# design.net
KiCad netlist of a schematic drawn in Altium Designer
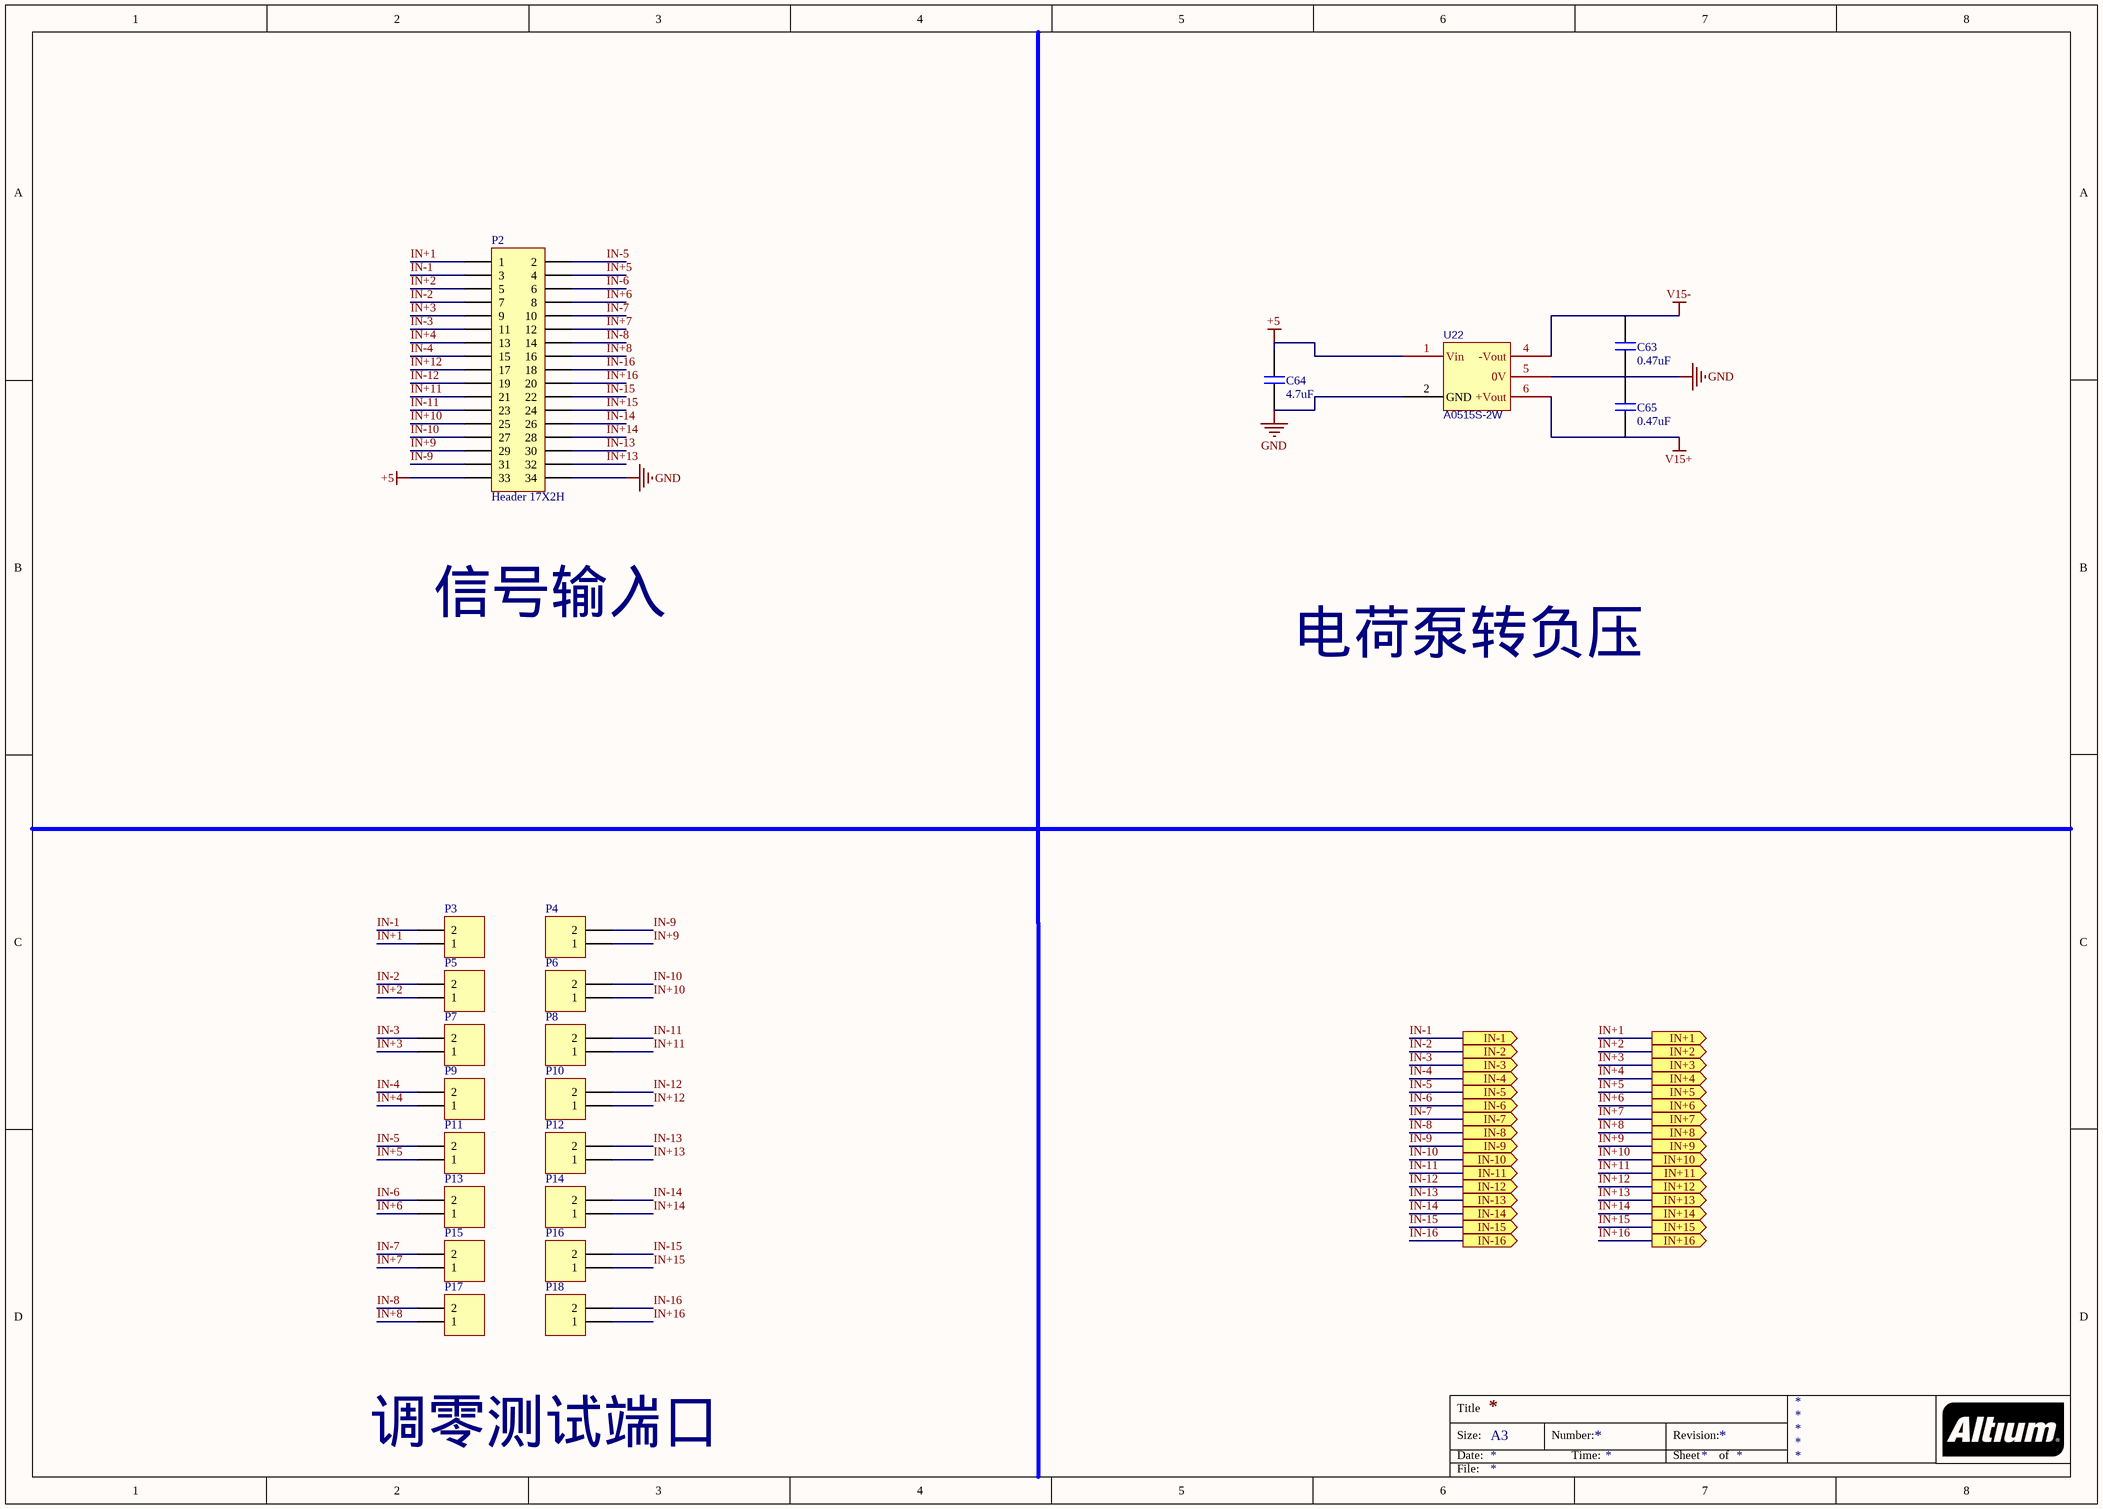
[diagram p0: 信号输入模块.SchDoc]

(export (version "E")
  (design (tool "Eeschema 10.0.6"))
  (components
    (comp (ref "C63")
      (value "0.47uF")
      (footprint "0805C")
      (description "普通电容")
      (libsource (lib "毕业设计") (part "CAP"))
    )
    (comp (ref "C64")
      (value "4.7uF")
      (footprint "0805C")
      (description "普通电容")
      (libsource (lib "毕业设计") (part "CAP"))
    )
    (comp (ref "C65")
      (value "0.47uF")
      (footprint "0805C")
      (description "普通电容")
      (libsource (lib "毕业设计") (part "CAP"))
    )
    (comp (ref "P2")
      (value "Header 17X2H")
      (footprint "HDR2X17")
      (description "Header, 17-Pin, Dual row, Right Angle")
      (fields (field (name "PUBLISHER") "Altium Limited"))
      (libsource (lib "Miscellaneous Connectors") (part "Header 17X2H"))
    )
    (comp (ref "P3")
      (value "Header 2H")
      (footprint "HDR-SMD_2P-P2.54-V-M-S4.8")
      (description "Header, 2-Pin, Right Angle")
      (fields (field (name "PUBLISHER") "Altium Limited"))
      (libsource (lib "") (part "Header 2H_1"))
    )
    (comp (ref "P4")
      (value "Header 2H")
      (footprint "HDR-SMD_2P-P2.54-V-M-S4.8")
      (description "Header, 2-Pin, Right Angle")
      (fields (field (name "PUBLISHER") "Altium Limited"))
      (libsource (lib "Miscellaneous Connectors") (part "Header 2H"))
    )
    (comp (ref "P5")
      (value "Header 2H")
      (footprint "HDR-SMD_2P-P2.54-V-M-S4.8")
      (description "Header, 2-Pin, Right Angle")
      (fields (field (name "PUBLISHER") "Altium Limited"))
      (libsource (lib "") (part "Header 2H_1"))
    )
    (comp (ref "P6")
      (value "Header 2H")
      (footprint "HDR-SMD_2P-P2.54-V-M-S4.8")
      (description "Header, 2-Pin, Right Angle")
      (fields (field (name "PUBLISHER") "Altium Limited"))
      (libsource (lib "Miscellaneous Connectors") (part "Header 2H"))
    )
    (comp (ref "P7")
      (value "Header 2H")
      (footprint "HDR-SMD_2P-P2.54-V-M-S4.8")
      (description "Header, 2-Pin, Right Angle")
      (fields (field (name "PUBLISHER") "Altium Limited"))
      (libsource (lib "") (part "Header 2H_1"))
    )
    (comp (ref "P8")
      (value "Header 2H")
      (footprint "HDR-SMD_2P-P2.54-V-M-S4.8")
      (description "Header, 2-Pin, Right Angle")
      (fields (field (name "PUBLISHER") "Altium Limited"))
      (libsource (lib "Miscellaneous Connectors") (part "Header 2H"))
    )
    (comp (ref "P9")
      (value "Header 2H")
      (footprint "HDR-SMD_2P-P2.54-V-M-S4.8")
      (description "Header, 2-Pin, Right Angle")
      (fields (field (name "PUBLISHER") "Altium Limited"))
      (libsource (lib "") (part "Header 2H_1"))
    )
    (comp (ref "P10")
      (value "Header 2H")
      (footprint "HDR-SMD_2P-P2.54-V-M-S4.8")
      (description "Header, 2-Pin, Right Angle")
      (fields (field (name "PUBLISHER") "Altium Limited"))
      (libsource (lib "Miscellaneous Connectors") (part "Header 2H"))
    )
    (comp (ref "P11")
      (value "Header 2H")
      (footprint "HDR-SMD_2P-P2.54-V-M-S4.8")
      (description "Header, 2-Pin, Right Angle")
      (fields (field (name "PUBLISHER") "Altium Limited"))
      (libsource (lib "") (part "Header 2H_1"))
    )
    (comp (ref "P12")
      (value "Header 2H")
      (footprint "HDR-SMD_2P-P2.54-V-M-S4.8")
      (description "Header, 2-Pin, Right Angle")
      (fields (field (name "PUBLISHER") "Altium Limited"))
      (libsource (lib "Miscellaneous Connectors") (part "Header 2H"))
    )
    (comp (ref "P13")
      (value "Header 2H")
      (footprint "HDR-SMD_2P-P2.54-V-M-S4.8")
      (description "Header, 2-Pin, Right Angle")
      (fields (field (name "PUBLISHER") "Altium Limited"))
      (libsource (lib "") (part "Header 2H_1"))
    )
    (comp (ref "P14")
      (value "Header 2H")
      (footprint "HDR-SMD_2P-P2.54-V-M-S4.8")
      (description "Header, 2-Pin, Right Angle")
      (fields (field (name "PUBLISHER") "Altium Limited"))
      (libsource (lib "Miscellaneous Connectors") (part "Header 2H"))
    )
    (comp (ref "P15")
      (value "Header 2H")
      (footprint "HDR-SMD_2P-P2.54-V-M-S4.8")
      (description "Header, 2-Pin, Right Angle")
      (fields (field (name "PUBLISHER") "Altium Limited"))
      (libsource (lib "") (part "Header 2H_1"))
    )
    (comp (ref "P16")
      (value "Header 2H")
      (footprint "HDR-SMD_2P-P2.54-V-M-S4.8")
      (description "Header, 2-Pin, Right Angle")
      (fields (field (name "PUBLISHER") "Altium Limited"))
      (libsource (lib "Miscellaneous Connectors") (part "Header 2H"))
    )
    (comp (ref "P17")
      (value "Header 2H")
      (footprint "HDR-SMD_2P-P2.54-V-M-S4.8")
      (description "Header, 2-Pin, Right Angle")
      (fields (field (name "PUBLISHER") "Altium Limited"))
      (libsource (lib "") (part "Header 2H_1"))
    )
    (comp (ref "P18")
      (value "Header 2H")
      (footprint "HDR-SMD_2P-P2.54-V-M-S4.8")
      (description "Header, 2-Pin, Right Angle")
      (fields (field (name "PUBLISHER") "Altium Limited"))
      (libsource (lib "Miscellaneous Connectors") (part "Header 2H"))
    )
    (comp (ref "U22")
      (value "A0515S-2W")
      (footprint "PWRM-TH_AXXXXS-2W")
      (description "5V升15V DC-DC")
      (fields (field (name "BOM_SUPPLIER PART") "C442557") (field (name "CONTRIBUTOR") "LCSC"))
      (libsource (lib "毕业设计") (part "A0515S-2W"))
    )
  )
  (nets
    (net (code "1") (name "+5") (class "Default")
      (node (ref "C64") (pin "2") (pinfunction "2_2") (pintype "passive"))
      (node (ref "P2") (pin "33") (pinfunction "33_33") (pintype "passive"))
      (node (ref "U22") (pin "1") (pinfunction "Vin_1") (pintype "passive"))
    )
    (net (code "2") (name "/IN+1") (class "Default")
      (node (ref "P2") (pin "1") (pinfunction "1_1") (pintype "passive"))
      (node (ref "P3") (pin "1") (pinfunction "1_1") (pintype "passive"))
    )
    (net (code "3") (name "/IN+2") (class "Default")
      (node (ref "P2") (pin "5") (pinfunction "5_5") (pintype "passive"))
      (node (ref "P5") (pin "1") (pinfunction "1_1") (pintype "passive"))
    )
    (net (code "4") (name "/IN+3") (class "Default")
      (node (ref "P2") (pin "9") (pinfunction "9_9") (pintype "passive"))
      (node (ref "P7") (pin "1") (pinfunction "1_1") (pintype "passive"))
    )
    (net (code "5") (name "/IN+4") (class "Default")
      (node (ref "P2") (pin "13") (pinfunction "13_13") (pintype "passive"))
      (node (ref "P9") (pin "1") (pinfunction "1_1") (pintype "passive"))
    )
    (net (code "6") (name "/IN+5") (class "Default")
      (node (ref "P11") (pin "1") (pinfunction "1_1") (pintype "passive"))
      (node (ref "P2") (pin "4") (pinfunction "4_4") (pintype "passive"))
    )
    (net (code "7") (name "/IN+6") (class "Default")
      (node (ref "P13") (pin "1") (pinfunction "1_1") (pintype "passive"))
      (node (ref "P2") (pin "8") (pinfunction "8_8") (pintype "passive"))
    )
    (net (code "8") (name "/IN+7") (class "Default")
      (node (ref "P15") (pin "1") (pinfunction "1_1") (pintype "passive"))
      (node (ref "P2") (pin "12") (pinfunction "12_12") (pintype "passive"))
    )
    (net (code "9") (name "/IN+8") (class "Default")
      (node (ref "P17") (pin "1") (pinfunction "1_1") (pintype "passive"))
      (node (ref "P2") (pin "16") (pinfunction "16_16") (pintype "passive"))
    )
    (net (code "10") (name "/IN+9") (class "Default")
      (node (ref "P2") (pin "29") (pinfunction "29_29") (pintype "passive"))
      (node (ref "P4") (pin "1") (pinfunction "1_1") (pintype "passive"))
    )
    (net (code "11") (name "/IN+10") (class "Default")
      (node (ref "P2") (pin "25") (pinfunction "25_25") (pintype "passive"))
      (node (ref "P6") (pin "1") (pinfunction "1_1") (pintype "passive"))
    )
    (net (code "12") (name "/IN+11") (class "Default")
      (node (ref "P2") (pin "21") (pinfunction "21_21") (pintype "passive"))
      (node (ref "P8") (pin "1") (pinfunction "1_1") (pintype "passive"))
    )
    (net (code "13") (name "/IN+12") (class "Default")
      (node (ref "P10") (pin "1") (pinfunction "1_1") (pintype "passive"))
      (node (ref "P2") (pin "17") (pinfunction "17_17") (pintype "passive"))
    )
    (net (code "14") (name "/IN+13") (class "Default")
      (node (ref "P12") (pin "1") (pinfunction "1_1") (pintype "passive"))
      (node (ref "P2") (pin "32") (pinfunction "32_32") (pintype "passive"))
    )
    (net (code "15") (name "/IN+14") (class "Default")
      (node (ref "P14") (pin "1") (pinfunction "1_1") (pintype "passive"))
      (node (ref "P2") (pin "28") (pinfunction "28_28") (pintype "passive"))
    )
    (net (code "16") (name "/IN+15") (class "Default")
      (node (ref "P16") (pin "1") (pinfunction "1_1") (pintype "passive"))
      (node (ref "P2") (pin "24") (pinfunction "24_24") (pintype "passive"))
    )
    (net (code "17") (name "/IN+16") (class "Default")
      (node (ref "P18") (pin "1") (pinfunction "1_1") (pintype "passive"))
      (node (ref "P2") (pin "20") (pinfunction "20_20") (pintype "passive"))
    )
    (net (code "18") (name "/IN-1") (class "Default")
      (node (ref "P2") (pin "3") (pinfunction "3_3") (pintype "passive"))
      (node (ref "P3") (pin "2") (pinfunction "2_2") (pintype "passive"))
    )
    (net (code "19") (name "/IN-2") (class "Default")
      (node (ref "P2") (pin "7") (pinfunction "7_7") (pintype "passive"))
      (node (ref "P5") (pin "2") (pinfunction "2_2") (pintype "passive"))
    )
    (net (code "20") (name "/IN-3") (class "Default")
      (node (ref "P2") (pin "11") (pinfunction "11_11") (pintype "passive"))
      (node (ref "P7") (pin "2") (pinfunction "2_2") (pintype "passive"))
    )
    (net (code "21") (name "/IN-4") (class "Default")
      (node (ref "P2") (pin "15") (pinfunction "15_15") (pintype "passive"))
      (node (ref "P9") (pin "2") (pinfunction "2_2") (pintype "passive"))
    )
    (net (code "22") (name "/IN-5") (class "Default")
      (node (ref "P11") (pin "2") (pinfunction "2_2") (pintype "passive"))
      (node (ref "P2") (pin "2") (pinfunction "2_2") (pintype "passive"))
    )
    (net (code "23") (name "/IN-6") (class "Default")
      (node (ref "P13") (pin "2") (pinfunction "2_2") (pintype "passive"))
      (node (ref "P2") (pin "6") (pinfunction "6_6") (pintype "passive"))
    )
    (net (code "24") (name "/IN-7") (class "Default")
      (node (ref "P15") (pin "2") (pinfunction "2_2") (pintype "passive"))
      (node (ref "P2") (pin "10") (pinfunction "10_10") (pintype "passive"))
    )
    (net (code "25") (name "/IN-8") (class "Default")
      (node (ref "P17") (pin "2") (pinfunction "2_2") (pintype "passive"))
      (node (ref "P2") (pin "14") (pinfunction "14_14") (pintype "passive"))
    )
    (net (code "26") (name "/IN-9") (class "Default")
      (node (ref "P2") (pin "31") (pinfunction "31_31") (pintype "passive"))
      (node (ref "P4") (pin "2") (pinfunction "2_2") (pintype "passive"))
    )
    (net (code "27") (name "/IN-10") (class "Default")
      (node (ref "P2") (pin "27") (pinfunction "27_27") (pintype "passive"))
      (node (ref "P6") (pin "2") (pinfunction "2_2") (pintype "passive"))
    )
    (net (code "28") (name "/IN-11") (class "Default")
      (node (ref "P2") (pin "23") (pinfunction "23_23") (pintype "passive"))
      (node (ref "P8") (pin "2") (pinfunction "2_2") (pintype "passive"))
    )
    (net (code "29") (name "/IN-12") (class "Default")
      (node (ref "P10") (pin "2") (pinfunction "2_2") (pintype "passive"))
      (node (ref "P2") (pin "19") (pinfunction "19_19") (pintype "passive"))
    )
    (net (code "30") (name "/IN-13") (class "Default")
      (node (ref "P12") (pin "2") (pinfunction "2_2") (pintype "passive"))
      (node (ref "P2") (pin "30") (pinfunction "30_30") (pintype "passive"))
    )
    (net (code "31") (name "/IN-14") (class "Default")
      (node (ref "P14") (pin "2") (pinfunction "2_2") (pintype "passive"))
      (node (ref "P2") (pin "26") (pinfunction "26_26") (pintype "passive"))
    )
    (net (code "32") (name "/IN-15") (class "Default")
      (node (ref "P16") (pin "2") (pinfunction "2_2") (pintype "passive"))
      (node (ref "P2") (pin "22") (pinfunction "22_22") (pintype "passive"))
    )
    (net (code "33") (name "/IN-16") (class "Default")
      (node (ref "P18") (pin "2") (pinfunction "2_2") (pintype "passive"))
      (node (ref "P2") (pin "18") (pinfunction "18_18") (pintype "passive"))
    )
    (net (code "34") (name "GND") (class "Default")
      (node (ref "C63") (pin "1") (pinfunction "1_1") (pintype "passive"))
      (node (ref "C64") (pin "1") (pinfunction "1_1") (pintype "passive"))
      (node (ref "C65") (pin "2") (pinfunction "2_2") (pintype "passive"))
      (node (ref "P2") (pin "34") (pinfunction "34_34") (pintype "passive"))
      (node (ref "U22") (pin "2") (pinfunction "GND_2") (pintype "passive"))
      (node (ref "U22") (pin "5") (pinfunction "0V_5") (pintype "passive"))
    )
    (net (code "35") (name "V15+") (class "Default")
      (node (ref "C65") (pin "1") (pinfunction "1_1") (pintype "passive"))
      (node (ref "U22") (pin "6") (pinfunction "+Vout_6") (pintype "passive"))
    )
    (net (code "36") (name "V15-") (class "Default")
      (node (ref "C63") (pin "2") (pinfunction "2_2") (pintype "passive"))
      (node (ref "U22") (pin "4") (pinfunction "-Vout_4") (pintype "passive"))
    )
  )
)
